# CVT_Temperature.net
KiCad netlist of a schematic drawn in Altium Designer
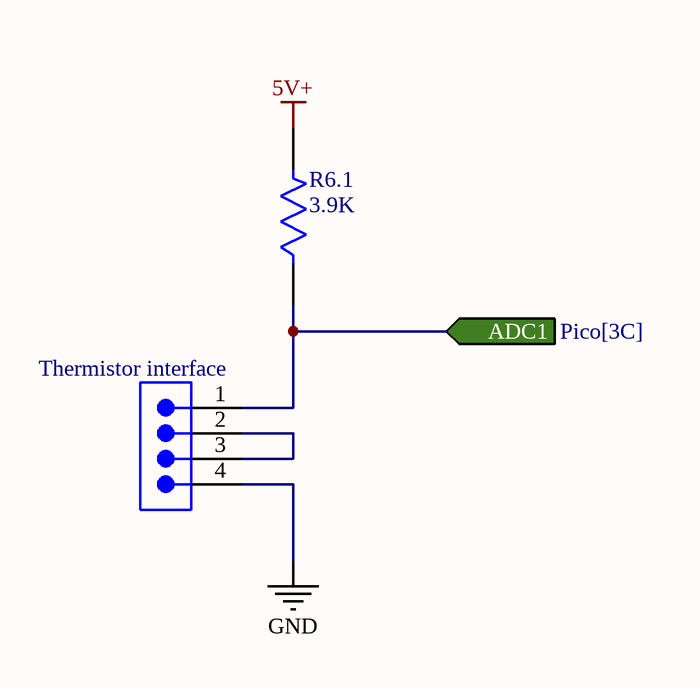
[diagram p0: CVT Temperature.SchDoc]

(export (version "E")
  (design (tool "Eeschema 10.0.6"))
  (components
    (comp (ref "R6.1")
      (value "3.9K")
      (footprint "FP-MFR-12-MFG")
      (description "RES MF 1/6W 1% AXIAL")
      (fields (field (name "TOLERANCE") "1%"))
      (libsource (lib "Altium Content Vault") (part "1029c3af85768c4190bb7ad29bc67b5"))
    )
    (comp (ref "Thermistor interface")
      (value "4 Pin Header")
      (footprint "SMTC-TSW-104-08-X-S")
      (description "0.025\" SQ Post Header, Through-hole, Vertical, -55 to 125 degC, 2.54 mm Pitch, 4-Pin, Male, RoHS")
      (fields (field (name "MANUFACTURER") "Samtec") (field (name "PARTNUMBER") "TSW-104-08-G-S"))
      (libsource (lib "Altium Content Vault") (part "SMTC-TSW-104-08-X-S"))
    )
  )
  (nets
    (net (code "1") (name "/ADC1") (class "Default")
      (node (ref "R6.1") (pin "1") (pinfunction "1_1") (pintype "passive"))
      (node (ref "Thermistor interface") (pin "1") (pinfunction "1_1") (pintype "passive"))
    )
    (net (code "2") (name "5V+") (class "Default")
      (node (ref "R6.1") (pin "2") (pinfunction "2_2") (pintype "passive"))
    )
    (net (code "3") (name "GND") (class "Default")
      (node (ref "Thermistor interface") (pin "4") (pinfunction "4_4") (pintype "passive"))
    )
    (net (code "4") (name "Net-(Thermistor interface-Pad2)") (class "Default")
      (node (ref "Thermistor interface") (pin "2") (pinfunction "2_2") (pintype "passive"))
      (node (ref "Thermistor interface") (pin "3") (pinfunction "3_3") (pintype "passive"))
    )
  )
)
